# SingleBoardDrone_Pow.net
KiCad netlist of a schematic drawn in Altium Designer
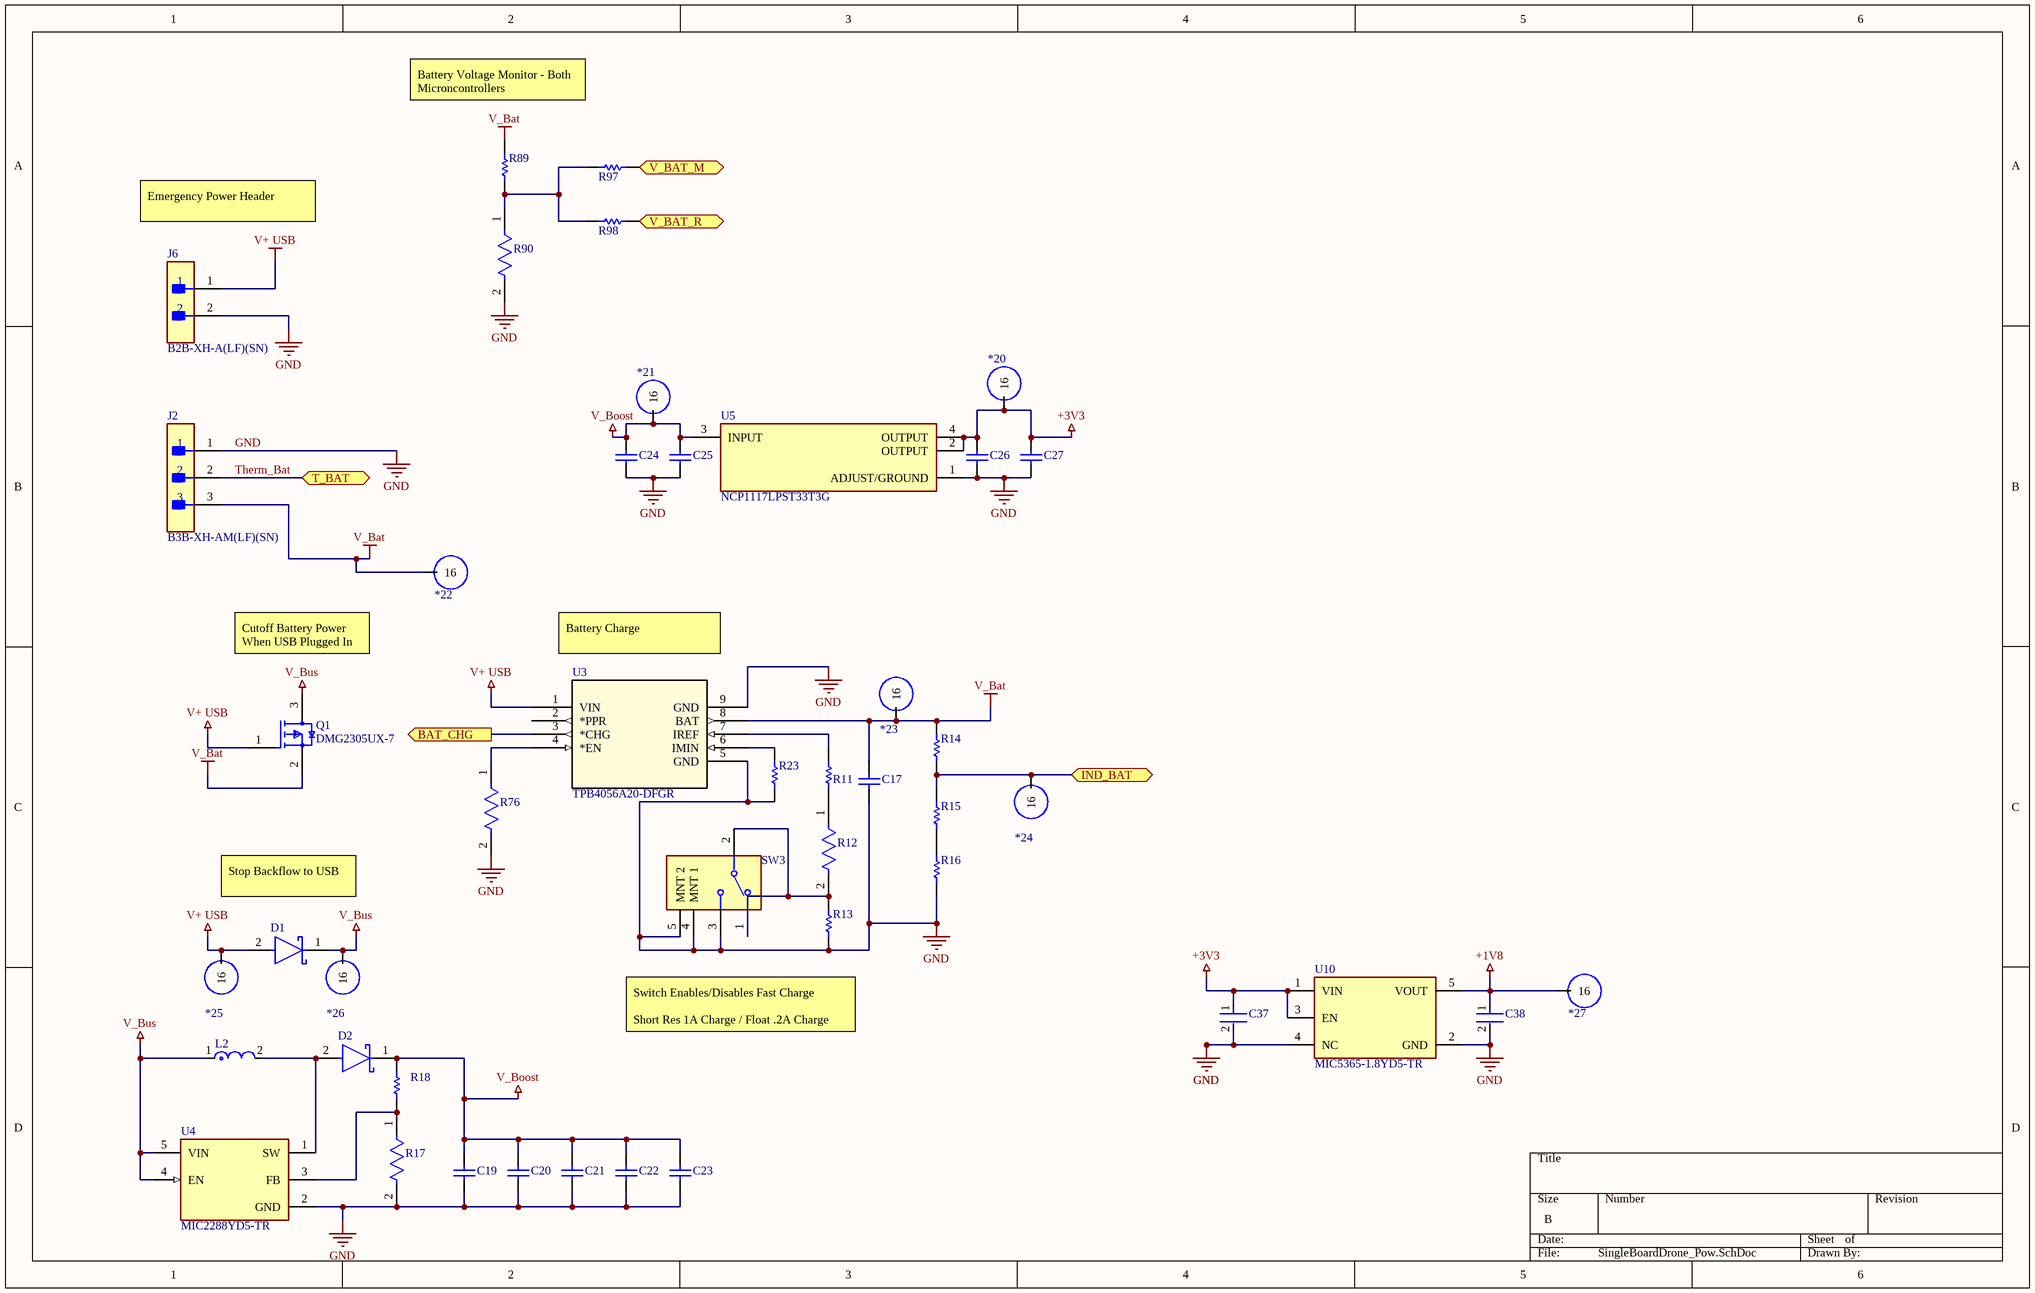
[diagram p0: SingleBoardDrone_Pow.SchDoc]

(export (version "E")
  (design (tool "Eeschema 10.0.6"))
  (components
    (comp (ref "*20")
      (value "Component_1")
      (footprint "Test_Point")
      (libsource (lib "Test_Point") (part "Component_1"))
    )
    (comp (ref "*21")
      (value "Component_1")
      (footprint "Test_Point")
      (libsource (lib "Test_Point") (part "Component_1"))
    )
    (comp (ref "*22")
      (value "Component_1")
      (footprint "Test_Point")
      (libsource (lib "Test_Point") (part "Component_1"))
    )
    (comp (ref "*23")
      (value "Component_1")
      (footprint "Test_Point")
      (libsource (lib "Test_Point") (part "Component_1"))
    )
    (comp (ref "*24")
      (value "Component_1")
      (footprint "Test_Point")
      (libsource (lib "Test_Point") (part "Component_1"))
    )
    (comp (ref "*25")
      (value "Component_1")
      (footprint "Test_Point")
      (libsource (lib "Test_Point") (part "Component_1"))
    )
    (comp (ref "*26")
      (value "Component_1")
      (footprint "Test_Point")
      (libsource (lib "Test_Point") (part "Component_1"))
    )
    (comp (ref "*27")
      (value "Component_1")
      (footprint "Test_Point")
      (libsource (lib "Test_Point") (part "Component_1"))
    )
    (comp (ref "C17")
      (value "CL10A475KQ8NNNC")
      (footprint "CAPC1608X90X30LL10T20")
      (description "Chip Capacitor, 4.7 uF, +/- 10%, 6.3 V, -55 to 85 degC, 0603 (1608 Metric), RoHS, Tape and Reel")
      (fields (field (name "MANUFACTURER") "Samsung Electro-Mechanics"))
      (libsource (lib "Altium Content Vault") (part "CAP-NP-2"))
    )
    (comp (ref "C19")
      (value "CL10A475KQ8NNNC")
      (footprint "CAPC1608X90X30LL10T20")
      (description "Chip Capacitor, 4.7 uF, +/- 10%, 6.3 V, -55 to 85 degC, 0603 (1608 Metric), RoHS, Tape and Reel")
      (fields (field (name "MANUFACTURER") "Samsung Electro-Mechanics"))
      (libsource (lib "Altium Content Vault") (part "CAP-NP-2"))
    )
    (comp (ref "C20")
      (value "CL10A475KQ8NNNC")
      (footprint "CAPC1608X90X30LL10T20")
      (description "Chip Capacitor, 4.7 uF, +/- 10%, 6.3 V, -55 to 85 degC, 0603 (1608 Metric), RoHS, Tape and Reel")
      (fields (field (name "MANUFACTURER") "Samsung Electro-Mechanics"))
      (libsource (lib "Altium Content Vault") (part "CAP-NP-2"))
    )
    (comp (ref "C21")
      (value "CL10A475KQ8NNNC")
      (footprint "CAPC1608X90X30LL10T20")
      (description "Chip Capacitor, 4.7 uF, +/- 10%, 6.3 V, -55 to 85 degC, 0603 (1608 Metric), RoHS, Tape and Reel")
      (fields (field (name "MANUFACTURER") "Samsung Electro-Mechanics"))
      (libsource (lib "Altium Content Vault") (part "CAP-NP-2"))
    )
    (comp (ref "C22")
      (value "CL10A475KQ8NNNC")
      (footprint "CAPC1608X90X30LL10T20")
      (description "Chip Capacitor, 4.7 uF, +/- 10%, 6.3 V, -55 to 85 degC, 0603 (1608 Metric), RoHS, Tape and Reel")
      (fields (field (name "MANUFACTURER") "Samsung Electro-Mechanics"))
      (libsource (lib "Altium Content Vault") (part "CAP-NP-2"))
    )
    (comp (ref "C23")
      (value "CL10A475KQ8NNNC")
      (footprint "CAPC1608X90X30LL10T20")
      (description "Chip Capacitor, 4.7 uF, +/- 10%, 6.3 V, -55 to 85 degC, 0603 (1608 Metric), RoHS, Tape and Reel")
      (fields (field (name "MANUFACTURER") "Samsung Electro-Mechanics"))
      (libsource (lib "Altium Content Vault") (part "CAP-NP-2"))
    )
    (comp (ref "C24")
      (value "CL10A475KQ8NNNC")
      (footprint "CAPC1608X90X30LL10T20")
      (description "Chip Capacitor, 4.7 uF, +/- 10%, 6.3 V, -55 to 85 degC, 0603 (1608 Metric), RoHS, Tape and Reel")
      (fields (field (name "MANUFACTURER") "Samsung Electro-Mechanics"))
      (libsource (lib "Altium Content Vault") (part "CAP-NP-2"))
    )
    (comp (ref "C25")
      (value "CL10A475KQ8NNNC")
      (footprint "CAPC1608X90X30LL10T20")
      (description "Chip Capacitor, 4.7 uF, +/- 10%, 6.3 V, -55 to 85 degC, 0603 (1608 Metric), RoHS, Tape and Reel")
      (fields (field (name "MANUFACTURER") "Samsung Electro-Mechanics"))
      (libsource (lib "Altium Content Vault") (part "CAP-NP-2"))
    )
    (comp (ref "C26")
      (value "CL10A475KQ8NNNC")
      (footprint "CAPC1608X90X30LL10T20")
      (description "Chip Capacitor, 4.7 uF, +/- 10%, 6.3 V, -55 to 85 degC, 0603 (1608 Metric), RoHS, Tape and Reel")
      (fields (field (name "MANUFACTURER") "Samsung Electro-Mechanics"))
      (libsource (lib "Altium Content Vault") (part "CAP-NP-2"))
    )
    (comp (ref "C27")
      (value "CL10A475KQ8NNNC")
      (footprint "CAPC1608X90X30LL10T20")
      (description "Chip Capacitor, 4.7 uF, +/- 10%, 6.3 V, -55 to 85 degC, 0603 (1608 Metric), RoHS, Tape and Reel")
      (fields (field (name "MANUFACTURER") "Samsung Electro-Mechanics"))
      (libsource (lib "Altium Content Vault") (part "CAP-NP-2"))
    )
    (comp (ref "C37")
      (value "CGA3E1X7R1E105K080AC")
      (footprint "FP-CGA3E-0_3-0_1-IPC_A")
      (description "Cap Ceramic 1uF 25V X7R 10% Pad SMD 0603 +125°C Automotive T/R")
      (fields (field (name "VOLTAGE") "25V") (field (name "TOLERANCE") "10%"))
      (libsource (lib "Altium Content Vault") (part "b4654b650e69147ec39a6b967a45e02"))
    )
    (comp (ref "C38")
      (value "CGA3E1X7R1E105K080AC")
      (footprint "FP-CGA3E-0_3-0_1-IPC_A")
      (description "Cap Ceramic 1uF 25V X7R 10% Pad SMD 0603 +125°C Automotive T/R")
      (fields (field (name "VOLTAGE") "25V") (field (name "TOLERANCE") "10%"))
      (libsource (lib "Altium Content Vault") (part "b4654b650e69147ec39a6b967a45e02"))
    )
    (comp (ref "D1")
      (value "PMEG3020DEP,115")
      (footprint "FP-SOD128-MFG")
      (description "DIODE SCHOTTKY 30V 2A SOD128")
      (libsource (lib "Altium Content Vault") (part "c1678fac7984e62e0809fbf79c06691"))
    )
    (comp (ref "D2")
      (value "PMEG3020DEP,115")
      (footprint "FP-SOD128-MFG")
      (description "DIODE SCHOTTKY 30V 2A SOD128")
      (libsource (lib "Altium Content Vault") (part "c1678fac7984e62e0809fbf79c06691"))
    )
    (comp (ref "J2")
      (value "B3B-XH-AM(LF)(SN)")
      (footprint "FP-B3B-XH-AM_LF_SN-MFG")
      (description "CONN HEADER VERT 3POS 2.5MM")
      (libsource (lib "Altium Content Vault") (part "0d3f023dd272f625e17a2be33dea85f"))
    )
    (comp (ref "J6")
      (value "B2B-XH-A(LF)(SN)")
      (footprint "FP-B2B-XH-A_LF_SN-MFG")
      (description "CONN HEADER VERT 2POS 2.5MM")
      (libsource (lib "Altium Content Vault") (part "3bc925449376181038e59eaffc5286c"))
    )
    (comp (ref "L2")
      (value "VLS5045EX-100M")
      (footprint "FP-VLS5045EX-100M-MFG")
      (description "FIXED IND 10UH 2.5A 79.3 MOHM")
      (fields (field (name "TOLERANCE") "20%"))
      (libsource (lib "Altium Content Vault") (part "4cc4b267dca4c8e51f7102f422741d8"))
    )
    (comp (ref "Q1")
      (value "DMG2305UX-7")
      (footprint "FP-SOT23-IPC_B")
      (description "MOSFET P-CH 20V 4.2A SOT23")
      (libsource (lib "Altium Content Vault") (part "87831b450059b469d4a68f5364f4496"))
    )
    (comp (ref "R11")
      (value "ERJ-6ENF2000V")
      (footprint "RESC2013X70X40ML20T20")
      (fields (field (name "MANUFACTURER") "Panasonic"))
      (libsource (lib "Altium Content Vault") (part "RES"))
    )
    (comp (ref "R12")
      (value "RMCF0402JT1K00")
      (footprint "FP-RMCF0402-IPC_B")
      (description "1kΩ ±5% 0.063W 0402 Thick Film Chip Resistor AEC-Q200 compliant")
      (fields (field (name "TOLERANCE") "5%"))
      (libsource (lib "Altium Content Vault") (part "1029c3af85768c4190bb7ad29bc67b5"))
    )
    (comp (ref "R13")
      (value "CRCW08055K00FKTA")
      (footprint "RESC2013X50X30ML20T20")
      (fields (field (name "MANUFACTURER") "Vishay Dale"))
      (libsource (lib "Altium Content Vault") (part "RES"))
    )
    (comp (ref "R14")
      (value "CRCW08055K00FKTA")
      (footprint "RESC2013X50X30ML20T20")
      (fields (field (name "MANUFACTURER") "Vishay Dale"))
      (libsource (lib "Altium Content Vault") (part "RES"))
    )
    (comp (ref "R15")
      (value "CRCW08055K00FKTA")
      (footprint "RESC2013X50X30ML20T20")
      (fields (field (name "MANUFACTURER") "Vishay Dale"))
      (libsource (lib "Altium Content Vault") (part "RES"))
    )
    (comp (ref "R16")
      (value "CRCW08055K00FKTA")
      (footprint "RESC2013X50X30ML20T20")
      (fields (field (name "MANUFACTURER") "Vishay Dale"))
      (libsource (lib "Altium Content Vault") (part "RES"))
    )
    (comp (ref "R17")
      (value "RMCF0402JT1K00")
      (footprint "FP-RMCF0402-IPC_B")
      (description "1kΩ ±5% 0.063W 0402 Thick Film Chip Resistor AEC-Q200 compliant")
      (fields (field (name "TOLERANCE") "5%"))
      (libsource (lib "Altium Content Vault") (part "1029c3af85768c4190bb7ad29bc67b5"))
    )
    (comp (ref "R18")
      (value "CRCW08055K00FKTA")
      (footprint "RESC2013X50X30ML20T20")
      (fields (field (name "MANUFACTURER") "Vishay Dale"))
      (libsource (lib "Altium Content Vault") (part "RES"))
    )
    (comp (ref "R23")
      (value "CRCW08055K00FKTA")
      (footprint "RESC2013X50X30ML20T20")
      (fields (field (name "MANUFACTURER") "Vishay Dale"))
      (libsource (lib "Altium Content Vault") (part "RES"))
    )
    (comp (ref "R76")
      (value "RC0402FR-070RL")
      (footprint "FP-RC0402-0_4-IPC_A")
      (description "RES SMD 0 OHM JUMPER 1/16W 0402")
      (fields (field (name "TOLERANCE") "1%"))
      (libsource (lib "Altium Content Vault") (part "1029c3af85768c4190bb7ad29bc67b5"))
    )
    (comp (ref "R89")
      (value "CRCW08055K00FKTA")
      (footprint "RESC2013X50X30ML20T20")
      (fields (field (name "MANUFACTURER") "Vishay Dale"))
      (libsource (lib "Altium Content Vault") (part "RES"))
    )
    (comp (ref "R90")
      (value "RMCF0603JG10K0")
      (footprint "FP-RMCF0603-MFG")
      (description "10kΩ ±5% 0.1W 0603 Thick Film Chip Resistor AEC-Q200 compliant")
      (fields (field (name "TOLERANCE") "5%"))
      (libsource (lib "Altium Content Vault") (part "1029c3af85768c4190bb7ad29bc67b5"))
    )
    (comp (ref "R97")
      (value "ERJ-6ENF2000V")
      (footprint "RESC2013X70X40ML20T20")
      (fields (field (name "MANUFACTURER") "Panasonic"))
      (libsource (lib "Altium Content Vault") (part "RES"))
    )
    (comp (ref "R98")
      (value "ERJ-6ENF2000V")
      (footprint "RESC2013X70X40ML20T20")
      (fields (field (name "MANUFACTURER") "Panasonic"))
      (libsource (lib "Altium Content Vault") (part "RES"))
    )
    (comp (ref "SW3")
      (value "1825232-1")
      (footprint "FP-1825232-1-MFG")
      (description "SWITCH SLIDE SPDT 200MA 30V")
      (fields
        (field (name "OCTOPART") "https://octopart.com/1825232-1-te+connectivity-45209882")
        (field (name "MANUFACTURER") "TE Connectivity")
      )
      (libsource (lib "Altium Content Vault") (part "b81b21e7de6c425a317152e587b8097"))
    )
    (comp (ref "U3")
      (value "TPB4056A20-DFGR")
      (footprint "TPB4056A20-DFGR:DFN2X2-8_TPK")
      (description "No Description Available")
      (fields (field (name "COPYRIGHT") "Copyright (C) 2025 Ultra Librarian. All rights reserved."))
      (libsource (lib "TPB4056A20-DFGR") (part "TPB4056A20-DFGR"))
    )
    (comp (ref "U4")
      (value "MIC2288YD5-TR")
      (footprint "FP-TSOT-5LD-PL-1-MFG")
      (description "IC REG BOOST ADJ 1.2A TSOT23-5")
      (libsource (lib "Altium Content Vault") (part "8b40e419ffb951c8150a61de73387bc"))
    )
    (comp (ref "U5")
      (value "NCP1117LPST33T3G")
      (footprint "FP-318H-MFG")
      (description "IC REG LINEAR 3.3V 1A SOT223")
      (libsource (lib "Altium Content Vault") (part "ba9dfc6f1948e29eb9591bef83395b3"))
    )
    (comp (ref "U10")
      (value "MIC5365-1.8YD5-TR")
      (footprint "FP-TSOT-5LD-PL-1-MFG")
      (description "MIC5365-1.8YD5-TR LDO Regulator Pos 1.8V 0.15A 5-Pin TSOT-23 T/R")
      (libsource (lib "Altium Content Vault") (part "49efecb8457b62bbb278fcbf558b656"))
    )
  )
  (nets
    (net (code "1") (name "+1V8") (class "Default")
      (node (ref "*27") (pin "TP1") (pinfunction "16_TP1") (pintype "passive"))
      (node (ref "C38") (pin "1") (pinfunction "1_1") (pintype "passive"))
      (node (ref "U10") (pin "5") (pinfunction "VOUT_5") (pintype "passive"))
    )
    (net (code "2") (name "+3V3") (class "Default")
      (node (ref "*20") (pin "TP1") (pinfunction "16_TP1") (pintype "passive"))
      (node (ref "C26") (pin "1") (pinfunction "1_1") (pintype "passive"))
      (node (ref "C27") (pin "1") (pinfunction "1_1") (pintype "passive"))
      (node (ref "C37") (pin "1") (pinfunction "1_1") (pintype "passive"))
      (node (ref "U10") (pin "1") (pinfunction "VIN_1") (pintype "power_in"))
      (node (ref "U10") (pin "3") (pinfunction "EN_3") (pintype "passive"))
      (node (ref "U5") (pin "2") (pinfunction "OUTPUT_2") (pintype "power_in"))
      (node (ref "U5") (pin "4") (pinfunction "OUTPUT_4") (pintype "power_in"))
    )
    (net (code "3") (name "/BAT_CHG") (class "Default")
      (node (ref "U3") (pin "3") (pinfunction "*CHG_3") (pintype "output"))
    )
    (net (code "4") (name "/IND_BAT") (class "Default")
      (node (ref "*24") (pin "TP1") (pinfunction "16_TP1") (pintype "passive"))
      (node (ref "R14") (pin "2") (pinfunction "2_2") (pintype "passive"))
      (node (ref "R15") (pin "1") (pinfunction "1_1") (pintype "passive"))
    )
    (net (code "5") (name "/Therm_Bat") (class "Default")
      (node (ref "J2") (pin "2") (pinfunction "2_2") (pintype "passive"))
    )
    (net (code "6") (name "/V_BAT_M") (class "Default")
      (node (ref "R97") (pin "1") (pinfunction "1_1") (pintype "passive"))
    )
    (net (code "7") (name "/V_BAT_R") (class "Default")
      (node (ref "R98") (pin "1") (pinfunction "1_1") (pintype "passive"))
    )
    (net (code "8") (name "GND") (class "Default")
      (node (ref "C17") (pin "2") (pinfunction "2_2") (pintype "passive"))
      (node (ref "C19") (pin "2") (pinfunction "2_2") (pintype "passive"))
      (node (ref "C20") (pin "2") (pinfunction "2_2") (pintype "passive"))
      (node (ref "C21") (pin "2") (pinfunction "2_2") (pintype "passive"))
      (node (ref "C22") (pin "2") (pinfunction "2_2") (pintype "passive"))
      (node (ref "C23") (pin "2") (pinfunction "2_2") (pintype "passive"))
      (node (ref "C24") (pin "2") (pinfunction "2_2") (pintype "passive"))
      (node (ref "C25") (pin "2") (pinfunction "2_2") (pintype "passive"))
      (node (ref "C26") (pin "2") (pinfunction "2_2") (pintype "passive"))
      (node (ref "C27") (pin "2") (pinfunction "2_2") (pintype "passive"))
      (node (ref "C37") (pin "2") (pinfunction "2_2") (pintype "passive"))
      (node (ref "C38") (pin "2") (pinfunction "2_2") (pintype "passive"))
      (node (ref "J2") (pin "1") (pinfunction "1_1") (pintype "passive"))
      (node (ref "J6") (pin "2") (pinfunction "2_2") (pintype "passive"))
      (node (ref "R13") (pin "2") (pinfunction "2_2") (pintype "passive"))
      (node (ref "R16") (pin "2") (pinfunction "2_2") (pintype "passive"))
      (node (ref "R17") (pin "2") (pinfunction "2_2") (pintype "passive"))
      (node (ref "R23") (pin "2") (pinfunction "2_2") (pintype "passive"))
      (node (ref "R76") (pin "2") (pinfunction "2_2") (pintype "passive"))
      (node (ref "R90") (pin "2") (pinfunction "2_2") (pintype "passive"))
      (node (ref "SW3") (pin "3") (pinfunction "3_3") (pintype "passive"))
      (node (ref "SW3") (pin "4") (pinfunction "MNT_1_4") (pintype "passive"))
      (node (ref "SW3") (pin "5") (pinfunction "MNT_2_5") (pintype "passive"))
      (node (ref "U10") (pin "2") (pinfunction "GND_2") (pintype "power_in"))
      (node (ref "U10") (pin "4") (pinfunction "NC_4") (pintype "passive"))
      (node (ref "U3") (pin "5") (pinfunction "GND_5") (pintype "power_in"))
      (node (ref "U3") (pin "9") (pinfunction "GND_9") (pintype "power_in"))
      (node (ref "U4") (pin "2") (pinfunction "GND_2") (pintype "power_in"))
      (node (ref "U5") (pin "1") (pinfunction "ADJUST/GROUND_1") (pintype "power_in"))
    )
    (net (code "9") (name "Net-(D2-A)") (class "Default")
      (node (ref "D2") (pin "2") (pinfunction "A_2") (pintype "passive"))
      (node (ref "L2") (pin "2") (pinfunction "2_2") (pintype "passive"))
      (node (ref "U4") (pin "1") (pinfunction "SW_1") (pintype "power_in"))
    )
    (net (code "10") (name "Net-(R11-Pad2)") (class "Default")
      (node (ref "R11") (pin "2") (pinfunction "2_2") (pintype "passive"))
      (node (ref "R12") (pin "1") (pinfunction "1_1") (pintype "passive"))
    )
    (net (code "11") (name "Net-(R12-Pad2)") (class "Default")
      (node (ref "R12") (pin "2") (pinfunction "2_2") (pintype "passive"))
      (node (ref "R13") (pin "1") (pinfunction "1_1") (pintype "passive"))
      (node (ref "SW3") (pin "1") (pinfunction "1_1") (pintype "passive"))
      (node (ref "SW3") (pin "2") (pinfunction "2_2") (pintype "passive"))
    )
    (net (code "12") (name "Net-(R15-Pad2)") (class "Default")
      (node (ref "R15") (pin "2") (pinfunction "2_2") (pintype "passive"))
      (node (ref "R16") (pin "1") (pinfunction "1_1") (pintype "passive"))
    )
    (net (code "13") (name "Net-(R89-Pad2)") (class "Default")
      (node (ref "R89") (pin "2") (pinfunction "2_2") (pintype "passive"))
      (node (ref "R90") (pin "1") (pinfunction "1_1") (pintype "passive"))
      (node (ref "R97") (pin "2") (pinfunction "2_2") (pintype "passive"))
      (node (ref "R98") (pin "2") (pinfunction "2_2") (pintype "passive"))
    )
    (net (code "14") (name "Net-(U3-*EN)") (class "Default")
      (node (ref "R76") (pin "1") (pinfunction "1_1") (pintype "passive"))
      (node (ref "U3") (pin "4") (pinfunction "*EN_4") (pintype "input"))
    )
    (net (code "15") (name "Net-(U3-IMIN)") (class "Default")
      (node (ref "R23") (pin "1") (pinfunction "1_1") (pintype "passive"))
      (node (ref "U3") (pin "6") (pinfunction "IMIN_6") (pintype "input"))
    )
    (net (code "16") (name "Net-(U3-IREF)") (class "Default")
      (node (ref "R11") (pin "1") (pinfunction "1_1") (pintype "passive"))
      (node (ref "U3") (pin "7") (pinfunction "IREF_7") (pintype "input"))
    )
    (net (code "17") (name "Net-(U4-FB)") (class "Default")
      (node (ref "R17") (pin "1") (pinfunction "1_1") (pintype "passive"))
      (node (ref "R18") (pin "2") (pinfunction "2_2") (pintype "passive"))
      (node (ref "U4") (pin "3") (pinfunction "FB_3") (pintype "passive"))
    )
    (net (code "18") (name "V+ USB") (class "Default")
      (node (ref "*25") (pin "TP1") (pinfunction "16_TP1") (pintype "passive"))
      (node (ref "D1") (pin "2") (pinfunction "A_2") (pintype "passive"))
      (node (ref "J6") (pin "1") (pinfunction "1_1") (pintype "passive"))
      (node (ref "Q1") (pin "1") (pinfunction "GATE_1") (pintype "passive"))
      (node (ref "U3") (pin "1") (pinfunction "VIN_1") (pintype "power_in"))
    )
    (net (code "19") (name "V_Bat") (class "Default")
      (node (ref "*22") (pin "TP1") (pinfunction "16_TP1") (pintype "passive"))
      (node (ref "*23") (pin "TP1") (pinfunction "16_TP1") (pintype "passive"))
      (node (ref "C17") (pin "1") (pinfunction "1_1") (pintype "passive"))
      (node (ref "J2") (pin "3") (pinfunction "3_3") (pintype "passive"))
      (node (ref "Q1") (pin "2") (pinfunction "SOURCE_2") (pintype "passive"))
      (node (ref "R14") (pin "1") (pinfunction "1_1") (pintype "passive"))
      (node (ref "R89") (pin "1") (pinfunction "1_1") (pintype "passive"))
      (node (ref "U3") (pin "8") (pinfunction "BAT_8") (pintype "output"))
    )
    (net (code "20") (name "V_Boost") (class "Default")
      (node (ref "*21") (pin "TP1") (pinfunction "16_TP1") (pintype "passive"))
      (node (ref "C19") (pin "1") (pinfunction "1_1") (pintype "passive"))
      (node (ref "C20") (pin "1") (pinfunction "1_1") (pintype "passive"))
      (node (ref "C21") (pin "1") (pinfunction "1_1") (pintype "passive"))
      (node (ref "C22") (pin "1") (pinfunction "1_1") (pintype "passive"))
      (node (ref "C23") (pin "1") (pinfunction "1_1") (pintype "passive"))
      (node (ref "C24") (pin "1") (pinfunction "1_1") (pintype "passive"))
      (node (ref "C25") (pin "1") (pinfunction "1_1") (pintype "passive"))
      (node (ref "D2") (pin "1") (pinfunction "C_1") (pintype "passive"))
      (node (ref "R18") (pin "1") (pinfunction "1_1") (pintype "passive"))
      (node (ref "U5") (pin "3") (pinfunction "INPUT_3") (pintype "power_in"))
    )
    (net (code "21") (name "V_Bus") (class "Default")
      (node (ref "*26") (pin "TP1") (pinfunction "16_TP1") (pintype "passive"))
      (node (ref "D1") (pin "1") (pinfunction "C_1") (pintype "passive"))
      (node (ref "L2") (pin "1") (pinfunction "1_1") (pintype "passive"))
      (node (ref "Q1") (pin "3") (pinfunction "DRAIN_3") (pintype "passive"))
      (node (ref "U4") (pin "4") (pinfunction "EN_4") (pintype "input"))
      (node (ref "U4") (pin "5") (pinfunction "VIN_5") (pintype "power_in"))
    )
    (net (code "22") (name "unconnected-(U3-*PPR-Pad2)") (class "Default")
      (node (ref "U3") (pin "2") (pinfunction "*PPR_2") (pintype "output"))
    )
  )
)
